# memoryboard5.net
KiCad netlist of a schematic drawn in EAGLE
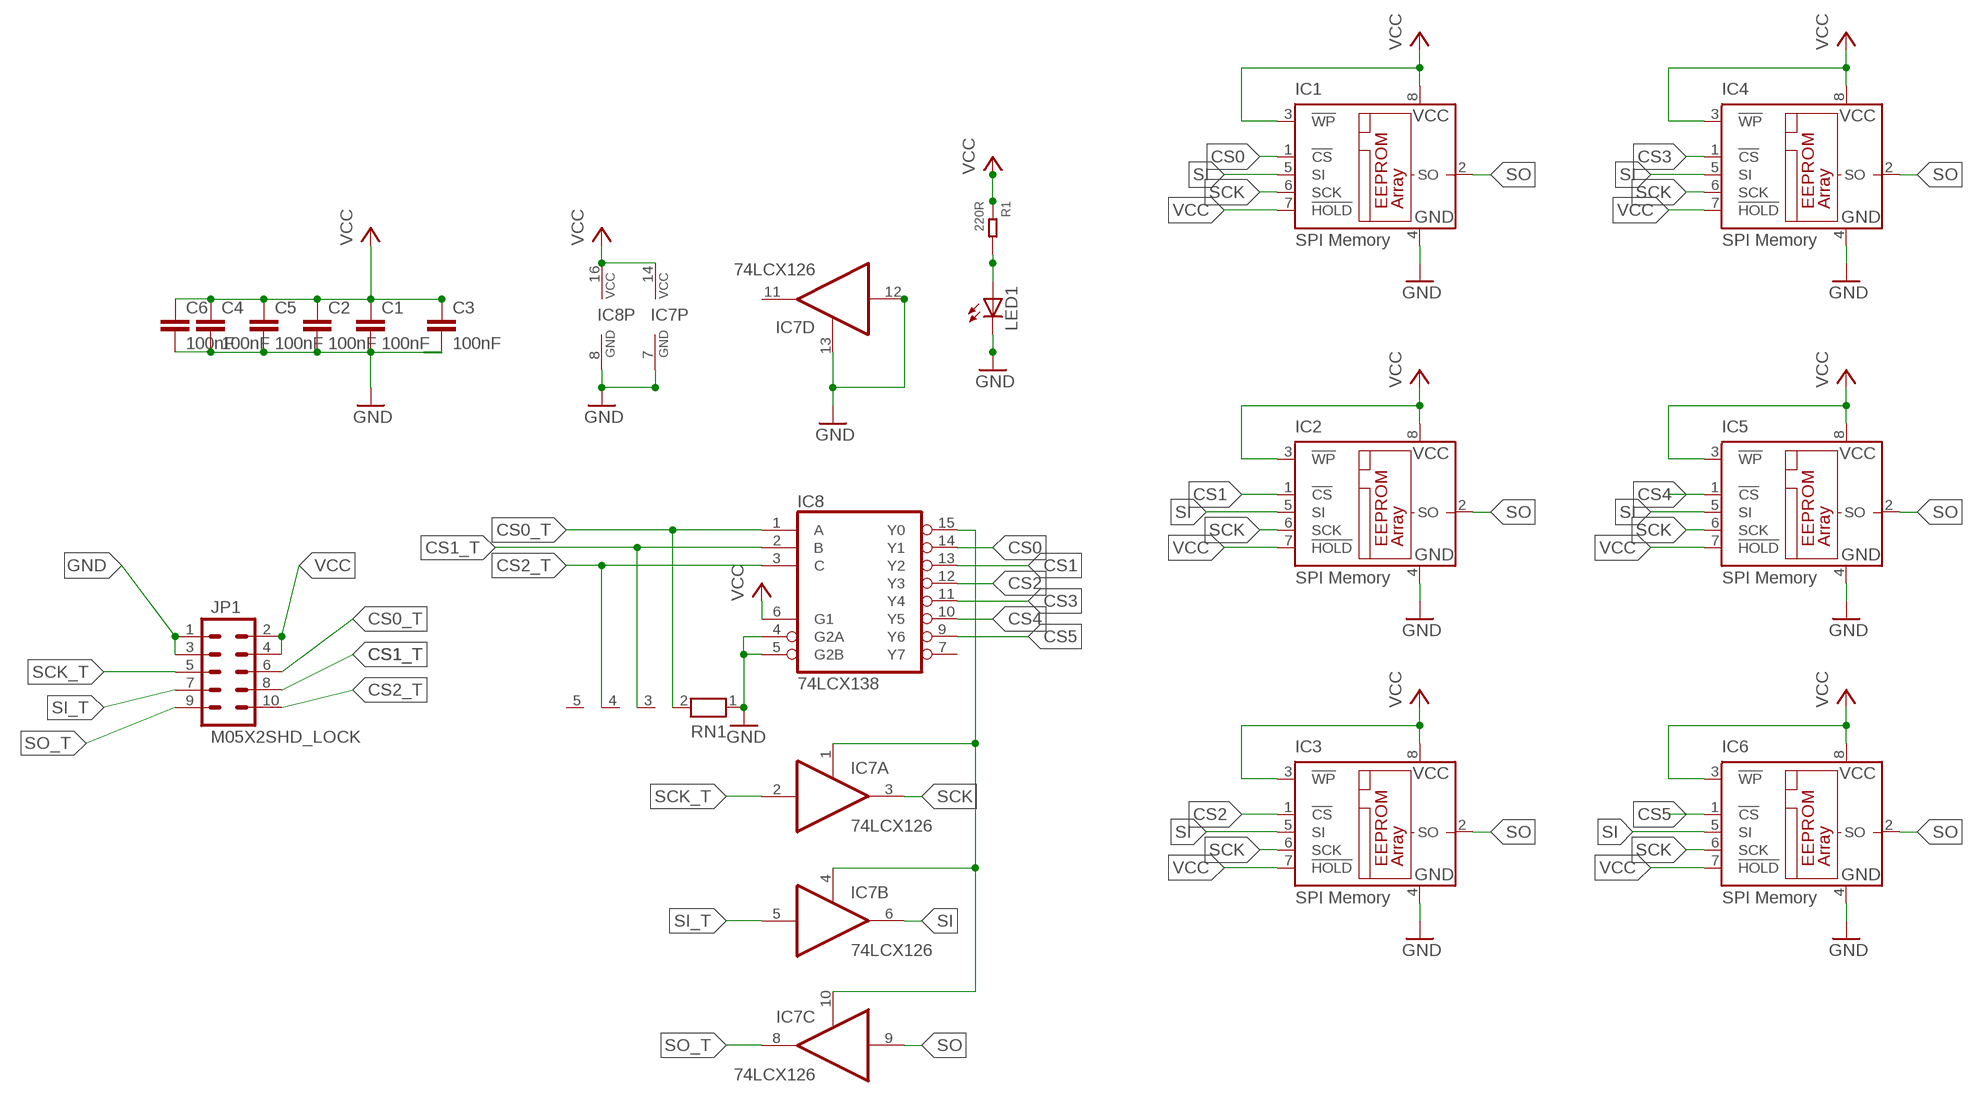
[diagram p0: schematic, sheet 1]

(export (version "E")
  (design (tool "Eeschema 10.0.6"))
  (components
    (comp (ref "C1")
      (value "100nF")
      (footprint "eagle-import:C0805")
      (libsource (lib "eagle-import") (part "C-EUC0805"))
    )
    (comp (ref "C2")
      (value "100nF")
      (footprint "eagle-import:C0805")
      (libsource (lib "eagle-import") (part "C-EUC0805"))
    )
    (comp (ref "C3")
      (value "100nF")
      (footprint "eagle-import:C0805")
      (libsource (lib "eagle-import") (part "C-EUC0805"))
    )
    (comp (ref "C4")
      (value "100nF")
      (footprint "eagle-import:C0805")
      (libsource (lib "eagle-import") (part "C-EUC0805"))
    )
    (comp (ref "C5")
      (value "100nF")
      (footprint "eagle-import:C0805")
      (libsource (lib "eagle-import") (part "C-EUC0805"))
    )
    (comp (ref "C6")
      (value "100nF")
      (footprint "eagle-import:C0805")
      (libsource (lib "eagle-import") (part "C-EUC0805"))
    )
    (comp (ref "IC1")
      (value "SPI Memory")
      (footprint "eagle-import:DIL8")
      (libsource (lib "eagle-import") (part "25PLC080"))
    )
    (comp (ref "IC2")
      (value "SPI Memory")
      (footprint "eagle-import:DIL8")
      (libsource (lib "eagle-import") (part "25PLC080"))
    )
    (comp (ref "IC3")
      (value "SPI Memory")
      (footprint "eagle-import:DIL8")
      (libsource (lib "eagle-import") (part "25PLC080"))
    )
    (comp (ref "IC4")
      (value "SPI Memory")
      (footprint "eagle-import:DIL8")
      (libsource (lib "eagle-import") (part "25PLC080"))
    )
    (comp (ref "IC5")
      (value "SPI Memory")
      (footprint "eagle-import:DIL8")
      (libsource (lib "eagle-import") (part "25PLC080"))
    )
    (comp (ref "IC6")
      (value "SPI Memory")
      (footprint "eagle-import:DIL8")
      (libsource (lib "eagle-import") (part "25PLC080"))
    )
    (comp (ref "IC7")
      (value "74LCX126")
      (footprint "eagle-import:DIL14")
      (libsource (lib "eagle-import") (part "74126NAC"))
    )
    (comp (ref "IC8")
      (value "74LCX138")
      (footprint "eagle-import:DIL16")
      (libsource (lib "eagle-import") (part "74138NHC"))
    )
    (comp (ref "JP1")
      (value "M05X2SHD_LOCK")
      (footprint "eagle-import:2X5-SHROUDED_LOCK")
      (libsource (lib "eagle-import") (part "M05X2SHD_LOCK"))
    )
    (comp (ref "LED1")
      (value "LED3MM")
      (footprint "eagle-import:LED3MM")
      (libsource (lib "eagle-import") (part "LED3MM"))
    )
    (comp (ref "R1")
      (value "220R")
      (footprint "eagle-import:R0805")
      (fields (field (name "MPN") "RC0805JR-07220RL"))
      (libsource (lib "eagle-import") (part "SMD-RES-220R-5%-1/8W(0805)"))
    )
    (comp (ref "RN1")
      (value "RN04")
      (footprint "eagle-import:RN-5")
      (libsource (lib "eagle-import") (part "RN04"))
    )
  )
  (nets
    (net (code "1") (name "CS0") (class "Default")
      (node (ref "IC1") (pin "1") (pinfunction "~{CS}_1") (pintype "input"))
      (node (ref "IC8") (pin "14") (pinfunction "Y1_14") (pintype "output"))
    )
    (net (code "2") (name "CS0_T") (class "Default")
      (node (ref "IC8") (pin "1") (pinfunction "A_1") (pintype "input"))
      (node (ref "JP1") (pin "6") (pinfunction "6_6") (pintype "passive"))
      (node (ref "RN1") (pin "2") (pinfunction "2_2") (pintype "passive"))
    )
    (net (code "3") (name "CS1") (class "Default")
      (node (ref "IC2") (pin "1") (pinfunction "~{CS}_1") (pintype "input"))
      (node (ref "IC8") (pin "13") (pinfunction "Y2_13") (pintype "output"))
    )
    (net (code "4") (name "CS1_T") (class "Default")
      (node (ref "IC8") (pin "2") (pinfunction "B_2") (pintype "input"))
      (node (ref "JP1") (pin "8") (pinfunction "8_8") (pintype "passive"))
      (node (ref "RN1") (pin "3") (pinfunction "3_3") (pintype "passive"))
    )
    (net (code "5") (name "CS2") (class "Default")
      (node (ref "IC3") (pin "1") (pinfunction "~{CS}_1") (pintype "input"))
      (node (ref "IC8") (pin "12") (pinfunction "Y3_12") (pintype "output"))
    )
    (net (code "6") (name "CS2_T") (class "Default")
      (node (ref "IC8") (pin "3") (pinfunction "C_3") (pintype "input"))
      (node (ref "JP1") (pin "10") (pinfunction "10_10") (pintype "passive"))
      (node (ref "RN1") (pin "4") (pinfunction "4_4") (pintype "passive"))
    )
    (net (code "7") (name "CS3") (class "Default")
      (node (ref "IC4") (pin "1") (pinfunction "~{CS}_1") (pintype "input"))
      (node (ref "IC8") (pin "11") (pinfunction "Y4_11") (pintype "output"))
    )
    (net (code "8") (name "CS4") (class "Default")
      (node (ref "IC5") (pin "1") (pinfunction "~{CS}_1") (pintype "input"))
      (node (ref "IC8") (pin "10") (pinfunction "Y5_10") (pintype "output"))
    )
    (net (code "9") (name "CS5") (class "Default")
      (node (ref "IC6") (pin "1") (pinfunction "~{CS}_1") (pintype "input"))
      (node (ref "IC8") (pin "9") (pinfunction "Y6_9") (pintype "output"))
    )
    (net (code "10") (name "GND") (class "Default")
      (node (ref "C1") (pin "2") (pinfunction "2_2") (pintype "passive"))
      (node (ref "C2") (pin "2") (pinfunction "2_2") (pintype "passive"))
      (node (ref "C3") (pin "2") (pinfunction "2_2") (pintype "passive"))
      (node (ref "C4") (pin "2") (pinfunction "2_2") (pintype "passive"))
      (node (ref "C5") (pin "2") (pinfunction "2_2") (pintype "passive"))
      (node (ref "C6") (pin "2") (pinfunction "2_2") (pintype "passive"))
      (node (ref "IC1") (pin "4") (pinfunction "GND_4") (pintype "power_in"))
      (node (ref "IC2") (pin "4") (pinfunction "GND_4") (pintype "power_in"))
      (node (ref "IC3") (pin "4") (pinfunction "GND_4") (pintype "power_in"))
      (node (ref "IC4") (pin "4") (pinfunction "GND_4") (pintype "power_in"))
      (node (ref "IC5") (pin "4") (pinfunction "GND_4") (pintype "power_in"))
      (node (ref "IC6") (pin "4") (pinfunction "GND_4") (pintype "power_in"))
      (node (ref "IC7") (pin "12") (pinfunction "I_12") (pintype "input"))
      (node (ref "IC7") (pin "13") (pinfunction "OE_13") (pintype "input"))
      (node (ref "IC7") (pin "7") (pinfunction "GND_7") (pintype "power_in"))
      (node (ref "IC8") (pin "4") (pinfunction "G2A_4") (pintype "input"))
      (node (ref "IC8") (pin "5") (pinfunction "G2B_5") (pintype "input"))
      (node (ref "IC8") (pin "8") (pinfunction "GND_8") (pintype "power_in"))
      (node (ref "JP1") (pin "1") (pinfunction "1_1") (pintype "passive"))
      (node (ref "JP1") (pin "3") (pinfunction "3_3") (pintype "passive"))
      (node (ref "LED1") (pin "K") (pinfunction "C_K") (pintype "passive"))
      (node (ref "RN1") (pin "1") (pinfunction "1_1") (pintype "passive"))
    )
    (net (code "11") (name "Net-(IC7A-OE)") (class "Default")
      (node (ref "IC7") (pin "1") (pinfunction "OE_1") (pintype "input"))
      (node (ref "IC7") (pin "10") (pinfunction "OE_10") (pintype "input"))
      (node (ref "IC7") (pin "4") (pinfunction "OE_4") (pintype "input"))
      (node (ref "IC8") (pin "15") (pinfunction "Y0_15") (pintype "output"))
    )
    (net (code "12") (name "Net-(LED1-PadA)") (class "Default")
      (node (ref "LED1") (pin "A") (pinfunction "A_A") (pintype "passive"))
      (node (ref "R1") (pin "2") (pinfunction "2_2") (pintype "passive"))
    )
    (net (code "13") (name "SCK") (class "Default")
      (node (ref "IC1") (pin "6") (pinfunction "SCK_6") (pintype "input"))
      (node (ref "IC2") (pin "6") (pinfunction "SCK_6") (pintype "input"))
      (node (ref "IC3") (pin "6") (pinfunction "SCK_6") (pintype "input"))
      (node (ref "IC4") (pin "6") (pinfunction "SCK_6") (pintype "input"))
      (node (ref "IC5") (pin "6") (pinfunction "SCK_6") (pintype "input"))
      (node (ref "IC6") (pin "6") (pinfunction "SCK_6") (pintype "input"))
      (node (ref "IC7") (pin "3") (pinfunction "O_3") (pintype "output"))
    )
    (net (code "14") (name "SCK_T") (class "Default")
      (node (ref "IC7") (pin "2") (pinfunction "I_2") (pintype "input"))
      (node (ref "JP1") (pin "5") (pinfunction "5_5") (pintype "passive"))
    )
    (net (code "15") (name "SI") (class "Default")
      (node (ref "IC1") (pin "5") (pinfunction "SI_5") (pintype "input"))
      (node (ref "IC2") (pin "5") (pinfunction "SI_5") (pintype "input"))
      (node (ref "IC3") (pin "5") (pinfunction "SI_5") (pintype "input"))
      (node (ref "IC4") (pin "5") (pinfunction "SI_5") (pintype "input"))
      (node (ref "IC5") (pin "5") (pinfunction "SI_5") (pintype "input"))
      (node (ref "IC6") (pin "5") (pinfunction "SI_5") (pintype "input"))
      (node (ref "IC7") (pin "6") (pinfunction "O_6") (pintype "output"))
    )
    (net (code "16") (name "SI_T") (class "Default")
      (node (ref "IC7") (pin "5") (pinfunction "I_5") (pintype "input"))
      (node (ref "JP1") (pin "7") (pinfunction "7_7") (pintype "passive"))
    )
    (net (code "17") (name "SO") (class "Default")
      (node (ref "IC1") (pin "2") (pinfunction "SO_2") (pintype "bidirectional"))
      (node (ref "IC2") (pin "2") (pinfunction "SO_2") (pintype "bidirectional"))
      (node (ref "IC3") (pin "2") (pinfunction "SO_2") (pintype "bidirectional"))
      (node (ref "IC4") (pin "2") (pinfunction "SO_2") (pintype "bidirectional"))
      (node (ref "IC5") (pin "2") (pinfunction "SO_2") (pintype "bidirectional"))
      (node (ref "IC6") (pin "2") (pinfunction "SO_2") (pintype "bidirectional"))
      (node (ref "IC7") (pin "9") (pinfunction "I_9") (pintype "input"))
    )
    (net (code "18") (name "SO_T") (class "Default")
      (node (ref "IC7") (pin "8") (pinfunction "O_8") (pintype "output"))
      (node (ref "JP1") (pin "9") (pinfunction "9_9") (pintype "passive"))
    )
    (net (code "19") (name "VCC") (class "Default")
      (node (ref "C1") (pin "1") (pinfunction "1_1") (pintype "passive"))
      (node (ref "C2") (pin "1") (pinfunction "1_1") (pintype "passive"))
      (node (ref "C3") (pin "1") (pinfunction "1_1") (pintype "passive"))
      (node (ref "C4") (pin "1") (pinfunction "1_1") (pintype "passive"))
      (node (ref "C5") (pin "1") (pinfunction "1_1") (pintype "passive"))
      (node (ref "C6") (pin "1") (pinfunction "1_1") (pintype "passive"))
      (node (ref "IC1") (pin "3") (pinfunction "~{WP}_3") (pintype "input"))
      (node (ref "IC1") (pin "7") (pinfunction "~{HOLD}_7") (pintype "input"))
      (node (ref "IC1") (pin "8") (pinfunction "VCC_8") (pintype "power_in"))
      (node (ref "IC2") (pin "3") (pinfunction "~{WP}_3") (pintype "input"))
      (node (ref "IC2") (pin "7") (pinfunction "~{HOLD}_7") (pintype "input"))
      (node (ref "IC2") (pin "8") (pinfunction "VCC_8") (pintype "power_in"))
      (node (ref "IC3") (pin "3") (pinfunction "~{WP}_3") (pintype "input"))
      (node (ref "IC3") (pin "7") (pinfunction "~{HOLD}_7") (pintype "input"))
      (node (ref "IC3") (pin "8") (pinfunction "VCC_8") (pintype "power_in"))
      (node (ref "IC4") (pin "3") (pinfunction "~{WP}_3") (pintype "input"))
      (node (ref "IC4") (pin "7") (pinfunction "~{HOLD}_7") (pintype "input"))
      (node (ref "IC4") (pin "8") (pinfunction "VCC_8") (pintype "power_in"))
      (node (ref "IC5") (pin "3") (pinfunction "~{WP}_3") (pintype "input"))
      (node (ref "IC5") (pin "7") (pinfunction "~{HOLD}_7") (pintype "input"))
      (node (ref "IC5") (pin "8") (pinfunction "VCC_8") (pintype "power_in"))
      (node (ref "IC6") (pin "3") (pinfunction "~{WP}_3") (pintype "input"))
      (node (ref "IC6") (pin "7") (pinfunction "~{HOLD}_7") (pintype "input"))
      (node (ref "IC6") (pin "8") (pinfunction "VCC_8") (pintype "power_in"))
      (node (ref "IC7") (pin "14") (pinfunction "VCC_14") (pintype "power_in"))
      (node (ref "IC8") (pin "16") (pinfunction "VCC_16") (pintype "power_in"))
      (node (ref "IC8") (pin "6") (pinfunction "G1_6") (pintype "input"))
      (node (ref "JP1") (pin "2") (pinfunction "2_2") (pintype "passive"))
      (node (ref "JP1") (pin "4") (pinfunction "4_4") (pintype "passive"))
      (node (ref "R1") (pin "1") (pinfunction "1_1") (pintype "passive"))
    )
    (net (code "20") (name "unconnected-(IC7D-O-Pad11)") (class "Default")
      (node (ref "IC7") (pin "11") (pinfunction "O_11") (pintype "output"))
    )
    (net (code "21") (name "unconnected-(IC8A-Y7-Pad7)") (class "Default")
      (node (ref "IC8") (pin "7") (pinfunction "Y7_7") (pintype "output"))
    )
    (net (code "22") (name "unconnected-(RN1-Pad5)") (class "Default")
      (node (ref "RN1") (pin "5") (pinfunction "5_5") (pintype "passive"))
    )
  )
)
